# RamyunControlBoard.net
KiCad netlist of a schematic drawn in EAGLE
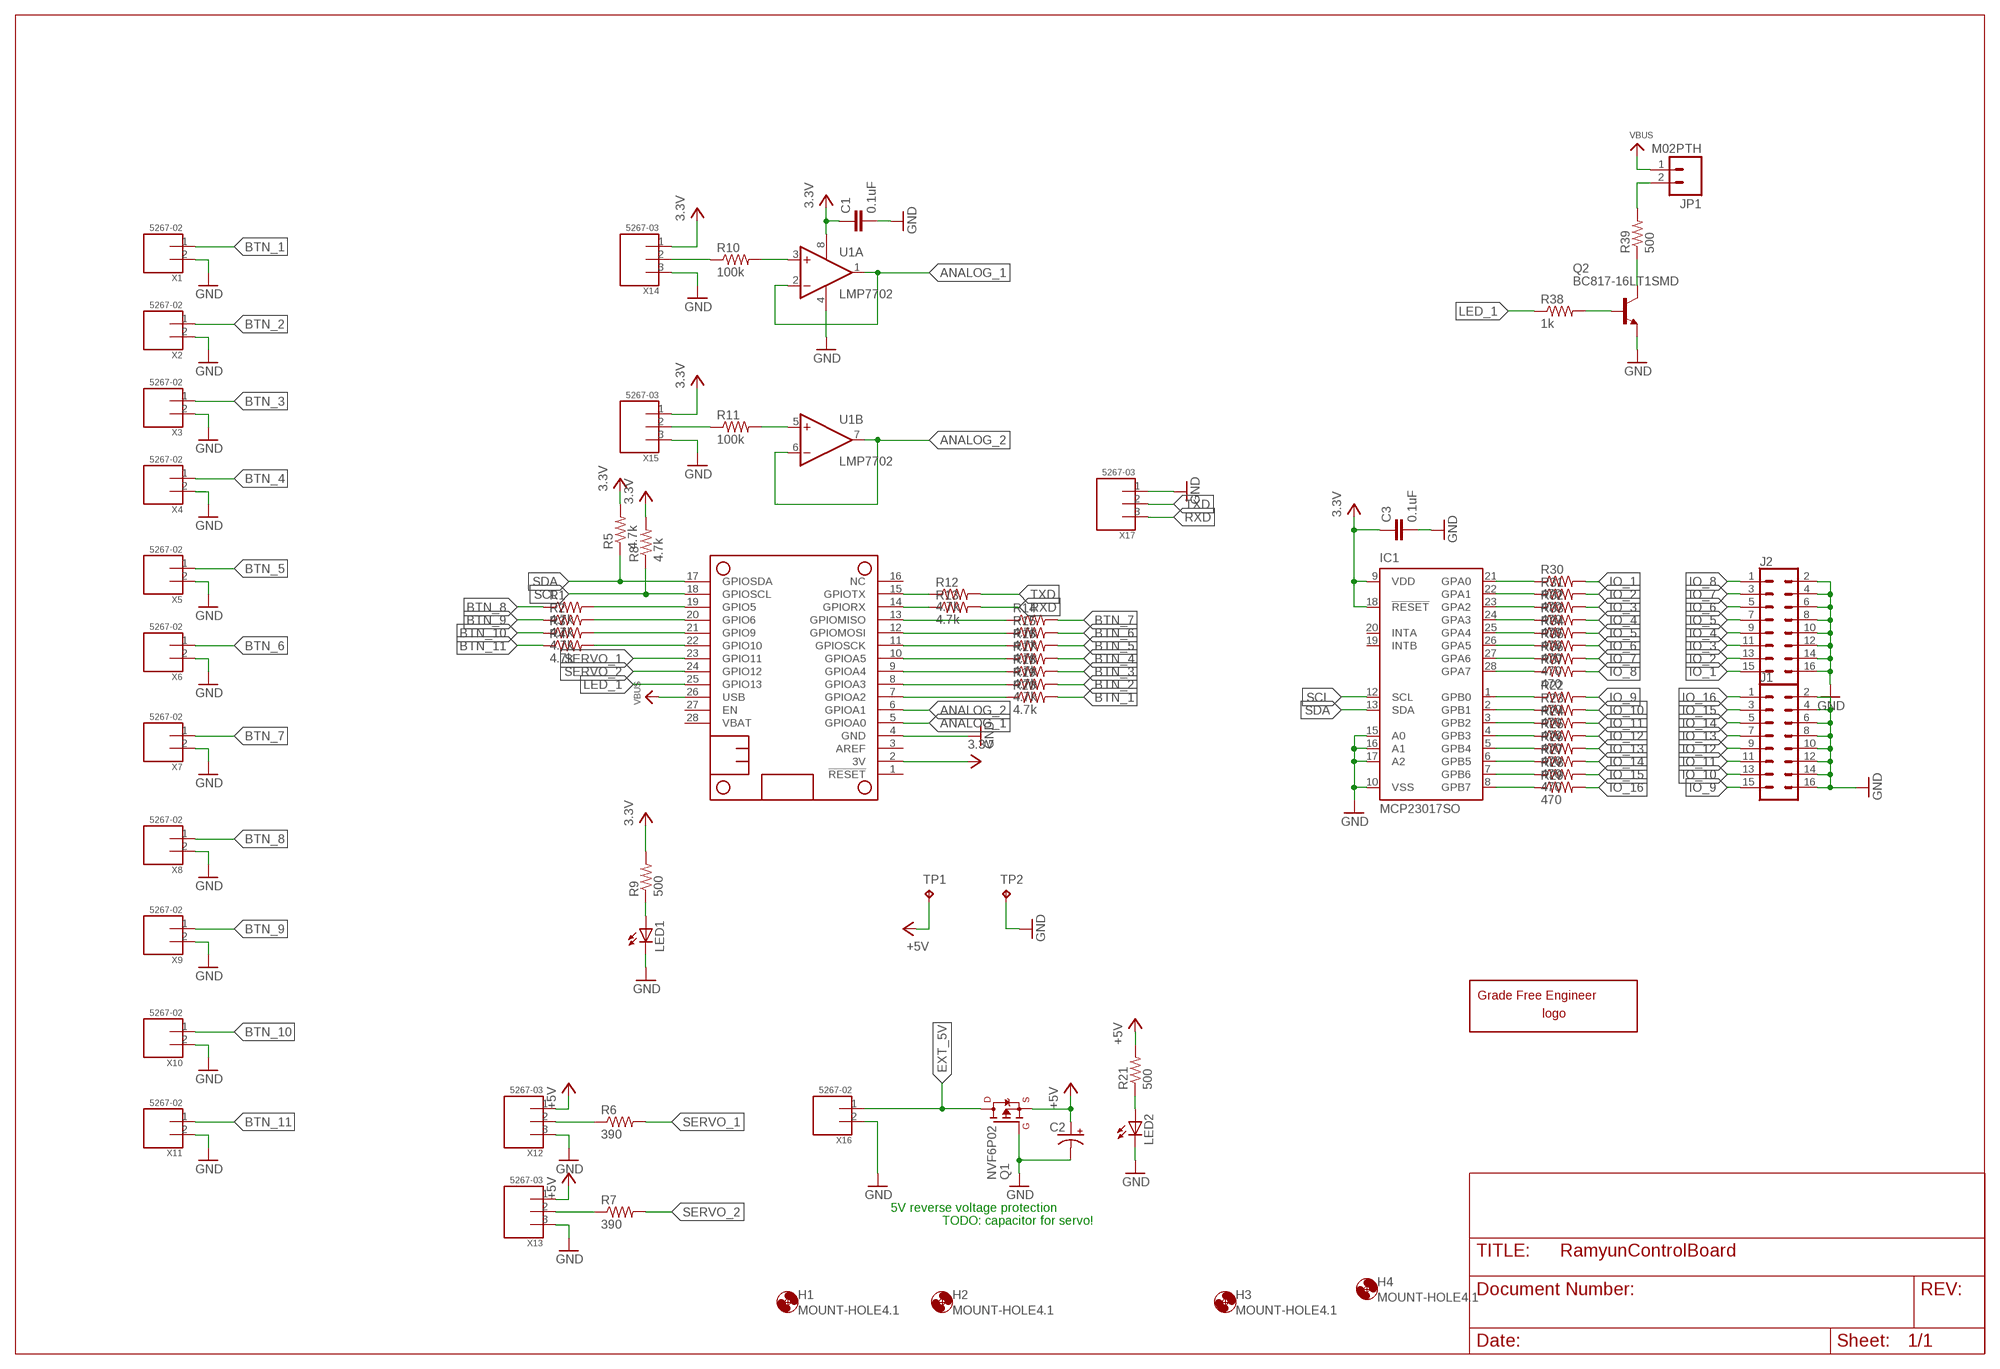
[diagram p0: schematic, sheet 1]

(export (version "E")
  (design (tool "Eeschema 10.0.6"))
  (components
    (comp (ref "C1")
      (value "0.1uF")
      (footprint "eagle-import:C0603(1608)_HANDSOLDER")
      (libsource (lib "eagle-import") (part "C0603(1608)_HAND"))
    )
    (comp (ref "C2")
      (value "CPOL-USE3.5-8")
      (footprint "eagle-import:E3,5-8")
      (libsource (lib "eagle-import") (part "CPOL-USE3.5-8"))
    )
    (comp (ref "C3")
      (value "0.1uF")
      (footprint "eagle-import:C0603(1608)_HANDSOLDER")
      (libsource (lib "eagle-import") (part "C0603(1608)_HAND"))
    )
    (comp (ref "H1")
      (value "MOUNT-HOLE4.1")
      (footprint "eagle-import:4,1")
      (libsource (lib "eagle-import") (part "MOUNT-HOLE4.1"))
    )
    (comp (ref "H2")
      (value "MOUNT-HOLE4.1")
      (footprint "eagle-import:4,1")
      (libsource (lib "eagle-import") (part "MOUNT-HOLE4.1"))
    )
    (comp (ref "H3")
      (value "MOUNT-HOLE4.1")
      (footprint "eagle-import:4,1")
      (libsource (lib "eagle-import") (part "MOUNT-HOLE4.1"))
    )
    (comp (ref "H4")
      (value "MOUNT-HOLE4.1")
      (footprint "eagle-import:4,1")
      (libsource (lib "eagle-import") (part "MOUNT-HOLE4.1"))
    )
    (comp (ref "IC1")
      (value "MCP23017SO")
      (footprint "eagle-import:SO28W")
      (libsource (lib "eagle-import") (part "MCP23017SO"))
    )
    (comp (ref "J1")
      (value "CONN_08X2")
      (footprint "eagle-import:2X8")
      (libsource (lib "eagle-import") (part "CONN_08X2"))
    )
    (comp (ref "J2")
      (value "CONN_08X2")
      (footprint "eagle-import:2X8")
      (libsource (lib "eagle-import") (part "CONN_08X2"))
    )
    (comp (ref "JP1")
      (value "M02PTH")
      (footprint "eagle-import:1X02")
      (libsource (lib "eagle-import") (part "M02PTH"))
    )
    (comp (ref "LED1")
      (value "LED3MM")
      (footprint "eagle-import:LED3MM")
      (libsource (lib "eagle-import") (part "LED3MM"))
    )
    (comp (ref "LED2")
      (value "LED3MM")
      (footprint "eagle-import:LED3MM")
      (libsource (lib "eagle-import") (part "LED3MM"))
    )
    (comp (ref "LOGO1")
      (value "GRADEFREELOGO-20")
      (footprint "eagle-import:GRADEFREELOGO-20")
      (libsource (lib "eagle-import") (part "GRADEFREELOGO-20"))
    )
    (comp (ref "MS1")
      (value "FEATHERWING_NODIM")
      (footprint "eagle-import:FEATHERWING_DIM")
      (libsource (lib "eagle-import") (part "FEATHERWING_NODIM"))
    )
    (comp (ref "Q1")
      (value "NVF6P02")
      (footprint "eagle-import:SOT223")
      (libsource (lib "eagle-import") (part "NVF6P02"))
    )
    (comp (ref "Q2")
      (value "BC817-16LT1SMD")
      (footprint "eagle-import:SOT23-BEC")
      (libsource (lib "eagle-import") (part "BC817SMD-16LT1"))
    )
    (comp (ref "R1")
      (value "4.7k")
      (footprint "eagle-import:R0603(1608)_HANDSOLDER")
      (libsource (lib "eagle-import") (part "R0603(1608)_HAND"))
    )
    (comp (ref "R2")
      (value "4.7k")
      (footprint "eagle-import:R0603(1608)_HANDSOLDER")
      (libsource (lib "eagle-import") (part "R0603(1608)_HAND"))
    )
    (comp (ref "R3")
      (value "4.7k")
      (footprint "eagle-import:R0603(1608)_HANDSOLDER")
      (libsource (lib "eagle-import") (part "R0603(1608)_HAND"))
    )
    (comp (ref "R4")
      (value "4.7k")
      (footprint "eagle-import:R0603(1608)_HANDSOLDER")
      (libsource (lib "eagle-import") (part "R0603(1608)_HAND"))
    )
    (comp (ref "R5")
      (value "4.7k")
      (footprint "eagle-import:R0603(1608)_HANDSOLDER")
      (libsource (lib "eagle-import") (part "R0603(1608)_HAND"))
    )
    (comp (ref "R6")
      (value "390")
      (footprint "eagle-import:R0603(1608)_HANDSOLDER")
      (libsource (lib "eagle-import") (part "R0603(1608)_HAND"))
    )
    (comp (ref "R7")
      (value "390")
      (footprint "eagle-import:R0603(1608)_HANDSOLDER")
      (libsource (lib "eagle-import") (part "R0603(1608)_HAND"))
    )
    (comp (ref "R8")
      (value "4.7k")
      (footprint "eagle-import:R0603(1608)_HANDSOLDER")
      (libsource (lib "eagle-import") (part "R0603(1608)_HAND"))
    )
    (comp (ref "R9")
      (value "500")
      (footprint "eagle-import:R0603(1608)_HANDSOLDER")
      (libsource (lib "eagle-import") (part "R0603(1608)_HAND"))
    )
    (comp (ref "R10")
      (value "100k")
      (footprint "eagle-import:R0603(1608)_HANDSOLDER")
      (libsource (lib "eagle-import") (part "R0603(1608)_HAND"))
    )
    (comp (ref "R11")
      (value "100k")
      (footprint "eagle-import:R0603(1608)_HANDSOLDER")
      (libsource (lib "eagle-import") (part "R0603(1608)_HAND"))
    )
    (comp (ref "R12")
      (value "4.7k")
      (footprint "eagle-import:R0603(1608)_HANDSOLDER")
      (libsource (lib "eagle-import") (part "R0603(1608)_HAND"))
    )
    (comp (ref "R13")
      (value "4.7k")
      (footprint "eagle-import:R0603(1608)_HANDSOLDER")
      (libsource (lib "eagle-import") (part "R0603(1608)_HAND"))
    )
    (comp (ref "R14")
      (value "4.7k")
      (footprint "eagle-import:R0603(1608)_HANDSOLDER")
      (libsource (lib "eagle-import") (part "R0603(1608)_HAND"))
    )
    (comp (ref "R15")
      (value "4.7k")
      (footprint "eagle-import:R0603(1608)_HANDSOLDER")
      (libsource (lib "eagle-import") (part "R0603(1608)_HAND"))
    )
    (comp (ref "R16")
      (value "4.7k")
      (footprint "eagle-import:R0603(1608)_HANDSOLDER")
      (libsource (lib "eagle-import") (part "R0603(1608)_HAND"))
    )
    (comp (ref "R17")
      (value "4.7k")
      (footprint "eagle-import:R0603(1608)_HANDSOLDER")
      (libsource (lib "eagle-import") (part "R0603(1608)_HAND"))
    )
    (comp (ref "R18")
      (value "4.7k")
      (footprint "eagle-import:R0603(1608)_HANDSOLDER")
      (libsource (lib "eagle-import") (part "R0603(1608)_HAND"))
    )
    (comp (ref "R19")
      (value "4.7k")
      (footprint "eagle-import:R0603(1608)_HANDSOLDER")
      (libsource (lib "eagle-import") (part "R0603(1608)_HAND"))
    )
    (comp (ref "R20")
      (value "4.7k")
      (footprint "eagle-import:R0603(1608)_HANDSOLDER")
      (libsource (lib "eagle-import") (part "R0603(1608)_HAND"))
    )
    (comp (ref "R21")
      (value "500")
      (footprint "eagle-import:R0603(1608)_HANDSOLDER")
      (libsource (lib "eagle-import") (part "R0603(1608)_HAND"))
    )
    (comp (ref "R22")
      (value "470")
      (footprint "eagle-import:R0603(1608)_HANDSOLDER")
      (libsource (lib "eagle-import") (part "R0603(1608)_HAND"))
    )
    (comp (ref "R23")
      (value "470")
      (footprint "eagle-import:R0603(1608)_HANDSOLDER")
      (libsource (lib "eagle-import") (part "R0603(1608)_HAND"))
    )
    (comp (ref "R24")
      (value "470")
      (footprint "eagle-import:R0603(1608)_HANDSOLDER")
      (libsource (lib "eagle-import") (part "R0603(1608)_HAND"))
    )
    (comp (ref "R25")
      (value "470")
      (footprint "eagle-import:R0603(1608)_HANDSOLDER")
      (libsource (lib "eagle-import") (part "R0603(1608)_HAND"))
    )
    (comp (ref "R26")
      (value "470")
      (footprint "eagle-import:R0603(1608)_HANDSOLDER")
      (libsource (lib "eagle-import") (part "R0603(1608)_HAND"))
    )
    (comp (ref "R27")
      (value "470")
      (footprint "eagle-import:R0603(1608)_HANDSOLDER")
      (libsource (lib "eagle-import") (part "R0603(1608)_HAND"))
    )
    (comp (ref "R28")
      (value "470")
      (footprint "eagle-import:R0603(1608)_HANDSOLDER")
      (libsource (lib "eagle-import") (part "R0603(1608)_HAND"))
    )
    (comp (ref "R29")
      (value "470")
      (footprint "eagle-import:R0603(1608)_HANDSOLDER")
      (libsource (lib "eagle-import") (part "R0603(1608)_HAND"))
    )
    (comp (ref "R30")
      (value "470")
      (footprint "eagle-import:R0603(1608)_HANDSOLDER")
      (libsource (lib "eagle-import") (part "R0603(1608)_HAND"))
    )
    (comp (ref "R31")
      (value "470")
      (footprint "eagle-import:R0603(1608)_HANDSOLDER")
      (libsource (lib "eagle-import") (part "R0603(1608)_HAND"))
    )
    (comp (ref "R32")
      (value "470")
      (footprint "eagle-import:R0603(1608)_HANDSOLDER")
      (libsource (lib "eagle-import") (part "R0603(1608)_HAND"))
    )
    (comp (ref "R33")
      (value "470")
      (footprint "eagle-import:R0603(1608)_HANDSOLDER")
      (libsource (lib "eagle-import") (part "R0603(1608)_HAND"))
    )
    (comp (ref "R34")
      (value "470")
      (footprint "eagle-import:R0603(1608)_HANDSOLDER")
      (libsource (lib "eagle-import") (part "R0603(1608)_HAND"))
    )
    (comp (ref "R35")
      (value "470")
      (footprint "eagle-import:R0603(1608)_HANDSOLDER")
      (libsource (lib "eagle-import") (part "R0603(1608)_HAND"))
    )
    (comp (ref "R36")
      (value "470")
      (footprint "eagle-import:R0603(1608)_HANDSOLDER")
      (libsource (lib "eagle-import") (part "R0603(1608)_HAND"))
    )
    (comp (ref "R37")
      (value "470")
      (footprint "eagle-import:R0603(1608)_HANDSOLDER")
      (libsource (lib "eagle-import") (part "R0603(1608)_HAND"))
    )
    (comp (ref "R38")
      (value "1k")
      (footprint "eagle-import:R0603(1608)_HANDSOLDER")
      (libsource (lib "eagle-import") (part "R0603(1608)_HAND"))
    )
    (comp (ref "R39")
      (value "500")
      (footprint "eagle-import:R0603(1608)_HANDSOLDER")
      (libsource (lib "eagle-import") (part "R0603(1608)_HAND"))
    )
    (comp (ref "TP1")
      (value "TP-5010")
      (footprint "eagle-import:TP-5010")
      (libsource (lib "eagle-import") (part "TP-5010"))
    )
    (comp (ref "TP2")
      (value "TP-5010")
      (footprint "eagle-import:TP-5010")
      (libsource (lib "eagle-import") (part "TP-5010"))
    )
    (comp (ref "U1")
      (value "LMP7702")
      (footprint "eagle-import:DGK_S-DPSO-G8")
      (libsource (lib "eagle-import") (part "LMP7702"))
    )
    (comp (ref "X1")
      (value "5267-02")
      (footprint "eagle-import:5267-02")
      (libsource (lib "eagle-import") (part "5267-02"))
    )
    (comp (ref "X2")
      (value "5267-02")
      (footprint "eagle-import:5267-02")
      (libsource (lib "eagle-import") (part "5267-02"))
    )
    (comp (ref "X3")
      (value "5267-02")
      (footprint "eagle-import:5267-02")
      (libsource (lib "eagle-import") (part "5267-02"))
    )
    (comp (ref "X4")
      (value "5267-02")
      (footprint "eagle-import:5267-02")
      (libsource (lib "eagle-import") (part "5267-02"))
    )
    (comp (ref "X5")
      (value "5267-02")
      (footprint "eagle-import:5267-02")
      (libsource (lib "eagle-import") (part "5267-02"))
    )
    (comp (ref "X6")
      (value "5267-02")
      (footprint "eagle-import:5267-02")
      (libsource (lib "eagle-import") (part "5267-02"))
    )
    (comp (ref "X7")
      (value "5267-02")
      (footprint "eagle-import:5267-02")
      (libsource (lib "eagle-import") (part "5267-02"))
    )
    (comp (ref "X8")
      (value "5267-02")
      (footprint "eagle-import:5267-02")
      (libsource (lib "eagle-import") (part "5267-02"))
    )
    (comp (ref "X9")
      (value "5267-02")
      (footprint "eagle-import:5267-02")
      (libsource (lib "eagle-import") (part "5267-02"))
    )
    (comp (ref "X10")
      (value "5267-02")
      (footprint "eagle-import:5267-02")
      (libsource (lib "eagle-import") (part "5267-02"))
    )
    (comp (ref "X11")
      (value "5267-02")
      (footprint "eagle-import:5267-02")
      (libsource (lib "eagle-import") (part "5267-02"))
    )
    (comp (ref "X12")
      (value "5267-03")
      (footprint "eagle-import:5267-03")
      (libsource (lib "eagle-import") (part "5267-03"))
    )
    (comp (ref "X13")
      (value "5267-03")
      (footprint "eagle-import:5267-03")
      (libsource (lib "eagle-import") (part "5267-03"))
    )
    (comp (ref "X14")
      (value "5267-03")
      (footprint "eagle-import:5267-03")
      (libsource (lib "eagle-import") (part "5267-03"))
    )
    (comp (ref "X15")
      (value "5267-03")
      (footprint "eagle-import:5267-03")
      (libsource (lib "eagle-import") (part "5267-03"))
    )
    (comp (ref "X16")
      (value "5267-02")
      (footprint "eagle-import:5267-02")
      (libsource (lib "eagle-import") (part "5267-02"))
    )
    (comp (ref "X17")
      (value "5267-03")
      (footprint "eagle-import:5267-03")
      (libsource (lib "eagle-import") (part "5267-03"))
    )
  )
  (nets
    (net (code "1") (name "+5V") (class "Default")
      (node (ref "C2") (pin "+") (pinfunction "+_+") (pintype "passive"))
      (node (ref "Q1") (pin "3") (pinfunction "S_3") (pintype "passive"))
      (node (ref "R21") (pin "2") (pinfunction "2_2") (pintype "passive"))
      (node (ref "TP1") (pin "TP") (pinfunction "TP_TP") (pintype "input"))
      (node (ref "X12") (pin "1") (pinfunction "1_1") (pintype "bidirectional"))
      (node (ref "X13") (pin "1") (pinfunction "1_1") (pintype "bidirectional"))
    )
    (net (code "2") (name "/VBAT") (class "Default")
      (node (ref "MS1") (pin "28") (pinfunction "VBAT_28") (pintype "power_in"))
    )
    (net (code "3") (name "3.3V") (class "Default")
      (node (ref "C1") (pin "1") (pinfunction "1_1") (pintype "passive"))
      (node (ref "C3") (pin "1") (pinfunction "1_1") (pintype "passive"))
      (node (ref "IC1") (pin "18") (pinfunction "~{RESET}_18") (pintype "input"))
      (node (ref "IC1") (pin "9") (pinfunction "VDD_9") (pintype "power_in"))
      (node (ref "MS1") (pin "2") (pinfunction "3V_2") (pintype "power_in"))
      (node (ref "R5") (pin "2") (pinfunction "2_2") (pintype "passive"))
      (node (ref "R8") (pin "2") (pinfunction "2_2") (pintype "passive"))
      (node (ref "R9") (pin "2") (pinfunction "2_2") (pintype "passive"))
      (node (ref "U1") (pin "8") (pinfunction "V+_8") (pintype "power_in"))
      (node (ref "X14") (pin "1") (pinfunction "1_1") (pintype "bidirectional"))
      (node (ref "X15") (pin "1") (pinfunction "1_1") (pintype "bidirectional"))
    )
    (net (code "4") (name "ANALOG_1") (class "Default")
      (node (ref "MS1") (pin "5") (pinfunction "GPIOA0_5") (pintype "bidirectional"))
      (node (ref "U1") (pin "1") (pinfunction "OUT_1") (pintype "output"))
      (node (ref "U1") (pin "2") (pinfunction "-IN_2") (pintype "input"))
    )
    (net (code "5") (name "ANALOG_2") (class "Default")
      (node (ref "MS1") (pin "6") (pinfunction "GPIOA1_6") (pintype "bidirectional"))
      (node (ref "U1") (pin "6") (pinfunction "-IN_6") (pintype "input"))
      (node (ref "U1") (pin "7") (pinfunction "OUT_7") (pintype "output"))
    )
    (net (code "6") (name "BTN_1") (class "Default")
      (node (ref "R20") (pin "2") (pinfunction "2_2") (pintype "passive"))
      (node (ref "X1") (pin "1") (pinfunction "1_1") (pintype "bidirectional"))
    )
    (net (code "7") (name "BTN_2") (class "Default")
      (node (ref "R19") (pin "2") (pinfunction "2_2") (pintype "passive"))
      (node (ref "X2") (pin "1") (pinfunction "1_1") (pintype "bidirectional"))
    )
    (net (code "8") (name "BTN_3") (class "Default")
      (node (ref "R18") (pin "2") (pinfunction "2_2") (pintype "passive"))
      (node (ref "X3") (pin "1") (pinfunction "1_1") (pintype "bidirectional"))
    )
    (net (code "9") (name "BTN_4") (class "Default")
      (node (ref "R17") (pin "2") (pinfunction "2_2") (pintype "passive"))
      (node (ref "X4") (pin "1") (pinfunction "1_1") (pintype "bidirectional"))
    )
    (net (code "10") (name "BTN_5") (class "Default")
      (node (ref "R16") (pin "2") (pinfunction "2_2") (pintype "passive"))
      (node (ref "X5") (pin "1") (pinfunction "1_1") (pintype "bidirectional"))
    )
    (net (code "11") (name "BTN_6") (class "Default")
      (node (ref "R15") (pin "2") (pinfunction "2_2") (pintype "passive"))
      (node (ref "X6") (pin "1") (pinfunction "1_1") (pintype "bidirectional"))
    )
    (net (code "12") (name "BTN_7") (class "Default")
      (node (ref "R14") (pin "2") (pinfunction "2_2") (pintype "passive"))
      (node (ref "X7") (pin "1") (pinfunction "1_1") (pintype "bidirectional"))
    )
    (net (code "13") (name "BTN_8") (class "Default")
      (node (ref "R1") (pin "1") (pinfunction "1_1") (pintype "passive"))
      (node (ref "X8") (pin "1") (pinfunction "1_1") (pintype "bidirectional"))
    )
    (net (code "14") (name "BTN_9") (class "Default")
      (node (ref "R2") (pin "1") (pinfunction "1_1") (pintype "passive"))
      (node (ref "X9") (pin "1") (pinfunction "1_1") (pintype "bidirectional"))
    )
    (net (code "15") (name "BTN_10") (class "Default")
      (node (ref "R3") (pin "1") (pinfunction "1_1") (pintype "passive"))
      (node (ref "X10") (pin "1") (pinfunction "1_1") (pintype "bidirectional"))
    )
    (net (code "16") (name "BTN_11") (class "Default")
      (node (ref "R4") (pin "1") (pinfunction "1_1") (pintype "passive"))
      (node (ref "X11") (pin "1") (pinfunction "1_1") (pintype "bidirectional"))
    )
    (net (code "17") (name "EXT_5V") (class "Default")
      (node (ref "Q1") (pin "2") (pinfunction "D_2") (pintype "passive"))
      (node (ref "Q1") (pin "4") (pinfunction "D_4") (pintype "passive"))
      (node (ref "X16") (pin "1") (pinfunction "1_1") (pintype "bidirectional"))
    )
    (net (code "18") (name "GND") (class "Default")
      (node (ref "C1") (pin "2") (pinfunction "2_2") (pintype "passive"))
      (node (ref "C2") (pin "-") (pinfunction "-_-") (pintype "passive"))
      (node (ref "C3") (pin "2") (pinfunction "2_2") (pintype "passive"))
      (node (ref "IC1") (pin "10") (pinfunction "VSS_10") (pintype "power_in"))
      (node (ref "IC1") (pin "15") (pinfunction "A0_15") (pintype "input"))
      (node (ref "IC1") (pin "16") (pinfunction "A1_16") (pintype "input"))
      (node (ref "IC1") (pin "17") (pinfunction "A2_17") (pintype "input"))
      (node (ref "J1") (pin "10") (pinfunction "10_10") (pintype "passive"))
      (node (ref "J1") (pin "12") (pinfunction "12_12") (pintype "passive"))
      (node (ref "J1") (pin "14") (pinfunction "14_14") (pintype "passive"))
      (node (ref "J1") (pin "16") (pinfunction "16_16") (pintype "passive"))
      (node (ref "J1") (pin "2") (pinfunction "2_2") (pintype "passive"))
      (node (ref "J1") (pin "4") (pinfunction "4_4") (pintype "passive"))
      (node (ref "J1") (pin "6") (pinfunction "6_6") (pintype "passive"))
      (node (ref "J1") (pin "8") (pinfunction "8_8") (pintype "passive"))
      (node (ref "J2") (pin "10") (pinfunction "10_10") (pintype "passive"))
      (node (ref "J2") (pin "12") (pinfunction "12_12") (pintype "passive"))
      (node (ref "J2") (pin "14") (pinfunction "14_14") (pintype "passive"))
      (node (ref "J2") (pin "16") (pinfunction "16_16") (pintype "passive"))
      (node (ref "J2") (pin "2") (pinfunction "2_2") (pintype "passive"))
      (node (ref "J2") (pin "4") (pinfunction "4_4") (pintype "passive"))
      (node (ref "J2") (pin "6") (pinfunction "6_6") (pintype "passive"))
      (node (ref "J2") (pin "8") (pinfunction "8_8") (pintype "passive"))
      (node (ref "LED1") (pin "K") (pinfunction "C_K") (pintype "passive"))
      (node (ref "LED2") (pin "K") (pinfunction "C_K") (pintype "passive"))
      (node (ref "MS1") (pin "4") (pinfunction "GND_4") (pintype "power_in"))
      (node (ref "Q1") (pin "1") (pinfunction "G_1") (pintype "passive"))
      (node (ref "Q2") (pin "E") (pinfunction "E_E") (pintype "passive"))
      (node (ref "TP2") (pin "TP") (pinfunction "TP_TP") (pintype "input"))
      (node (ref "U1") (pin "4") (pinfunction "V-_4") (pintype "power_in"))
      (node (ref "X1") (pin "2") (pinfunction "2_2") (pintype "bidirectional"))
      (node (ref "X10") (pin "2") (pinfunction "2_2") (pintype "bidirectional"))
      (node (ref "X11") (pin "2") (pinfunction "2_2") (pintype "bidirectional"))
      (node (ref "X12") (pin "3") (pinfunction "3_3") (pintype "bidirectional"))
      (node (ref "X13") (pin "3") (pinfunction "3_3") (pintype "bidirectional"))
      (node (ref "X14") (pin "3") (pinfunction "3_3") (pintype "bidirectional"))
      (node (ref "X15") (pin "3") (pinfunction "3_3") (pintype "bidirectional"))
      (node (ref "X16") (pin "2") (pinfunction "2_2") (pintype "bidirectional"))
      (node (ref "X17") (pin "1") (pinfunction "1_1") (pintype "bidirectional"))
      (node (ref "X2") (pin "2") (pinfunction "2_2") (pintype "bidirectional"))
      (node (ref "X3") (pin "2") (pinfunction "2_2") (pintype "bidirectional"))
      (node (ref "X4") (pin "2") (pinfunction "2_2") (pintype "bidirectional"))
      (node (ref "X5") (pin "2") (pinfunction "2_2") (pintype "bidirectional"))
      (node (ref "X6") (pin "2") (pinfunction "2_2") (pintype "bidirectional"))
      (node (ref "X7") (pin "2") (pinfunction "2_2") (pintype "bidirectional"))
      (node (ref "X8") (pin "2") (pinfunction "2_2") (pintype "bidirectional"))
      (node (ref "X9") (pin "2") (pinfunction "2_2") (pintype "bidirectional"))
    )
    (net (code "19") (name "IO_1") (class "Default")
      (node (ref "J2") (pin "15") (pinfunction "15_15") (pintype "passive"))
      (node (ref "R30") (pin "2") (pinfunction "2_2") (pintype "passive"))
    )
    (net (code "20") (name "IO_2") (class "Default")
      (node (ref "J2") (pin "13") (pinfunction "13_13") (pintype "passive"))
      (node (ref "R31") (pin "2") (pinfunction "2_2") (pintype "passive"))
    )
    (net (code "21") (name "IO_3") (class "Default")
      (node (ref "J2") (pin "11") (pinfunction "11_11") (pintype "passive"))
      (node (ref "R32") (pin "2") (pinfunction "2_2") (pintype "passive"))
    )
    (net (code "22") (name "IO_4") (class "Default")
      (node (ref "J2") (pin "9") (pinfunction "9_9") (pintype "passive"))
      (node (ref "R33") (pin "2") (pinfunction "2_2") (pintype "passive"))
    )
    (net (code "23") (name "IO_5") (class "Default")
      (node (ref "J2") (pin "7") (pinfunction "7_7") (pintype "passive"))
      (node (ref "R34") (pin "2") (pinfunction "2_2") (pintype "passive"))
    )
    (net (code "24") (name "IO_6") (class "Default")
      (node (ref "J2") (pin "5") (pinfunction "5_5") (pintype "passive"))
      (node (ref "R35") (pin "2") (pinfunction "2_2") (pintype "passive"))
    )
    (net (code "25") (name "IO_7") (class "Default")
      (node (ref "J2") (pin "3") (pinfunction "3_3") (pintype "passive"))
      (node (ref "R36") (pin "2") (pinfunction "2_2") (pintype "passive"))
    )
    (net (code "26") (name "IO_8") (class "Default")
      (node (ref "J2") (pin "1") (pinfunction "1_1") (pintype "passive"))
      (node (ref "R37") (pin "2") (pinfunction "2_2") (pintype "passive"))
    )
    (net (code "27") (name "IO_9") (class "Default")
      (node (ref "J1") (pin "15") (pinfunction "15_15") (pintype "passive"))
      (node (ref "R22") (pin "2") (pinfunction "2_2") (pintype "passive"))
    )
    (net (code "28") (name "IO_10") (class "Default")
      (node (ref "J1") (pin "13") (pinfunction "13_13") (pintype "passive"))
      (node (ref "R23") (pin "2") (pinfunction "2_2") (pintype "passive"))
    )
    (net (code "29") (name "IO_11") (class "Default")
      (node (ref "J1") (pin "11") (pinfunction "11_11") (pintype "passive"))
      (node (ref "R24") (pin "2") (pinfunction "2_2") (pintype "passive"))
    )
    (net (code "30") (name "IO_12") (class "Default")
      (node (ref "J1") (pin "9") (pinfunction "9_9") (pintype "passive"))
      (node (ref "R25") (pin "2") (pinfunction "2_2") (pintype "passive"))
    )
    (net (code "31") (name "IO_13") (class "Default")
      (node (ref "J1") (pin "7") (pinfunction "7_7") (pintype "passive"))
      (node (ref "R26") (pin "2") (pinfunction "2_2") (pintype "passive"))
    )
    (net (code "32") (name "IO_14") (class "Default")
      (node (ref "J1") (pin "5") (pinfunction "5_5") (pintype "passive"))
      (node (ref "R27") (pin "2") (pinfunction "2_2") (pintype "passive"))
    )
    (net (code "33") (name "IO_15") (class "Default")
      (node (ref "J1") (pin "3") (pinfunction "3_3") (pintype "passive"))
      (node (ref "R28") (pin "2") (pinfunction "2_2") (pintype "passive"))
    )
    (net (code "34") (name "IO_16") (class "Default")
      (node (ref "J1") (pin "1") (pinfunction "1_1") (pintype "passive"))
      (node (ref "R29") (pin "2") (pinfunction "2_2") (pintype "passive"))
    )
    (net (code "35") (name "LED_1") (class "Default")
      (node (ref "MS1") (pin "25") (pinfunction "GPIO13_25") (pintype "bidirectional"))
      (node (ref "R38") (pin "1") (pinfunction "1_1") (pintype "passive"))
    )
    (net (code "36") (name "Net-(IC1-GPA0)") (class "Default")
      (node (ref "IC1") (pin "21") (pinfunction "GPA0_21") (pintype "bidirectional"))
      (node (ref "R30") (pin "1") (pinfunction "1_1") (pintype "passive"))
    )
    (net (code "37") (name "Net-(IC1-GPA1)") (class "Default")
      (node (ref "IC1") (pin "22") (pinfunction "GPA1_22") (pintype "bidirectional"))
      (node (ref "R31") (pin "1") (pinfunction "1_1") (pintype "passive"))
    )
    (net (code "38") (name "Net-(IC1-GPA2)") (class "Default")
      (node (ref "IC1") (pin "23") (pinfunction "GPA2_23") (pintype "bidirectional"))
      (node (ref "R32") (pin "1") (pinfunction "1_1") (pintype "passive"))
    )
    (net (code "39") (name "Net-(IC1-GPA3)") (class "Default")
      (node (ref "IC1") (pin "24") (pinfunction "GPA3_24") (pintype "bidirectional"))
      (node (ref "R33") (pin "1") (pinfunction "1_1") (pintype "passive"))
    )
    (net (code "40") (name "Net-(IC1-GPA4)") (class "Default")
      (node (ref "IC1") (pin "25") (pinfunction "GPA4_25") (pintype "bidirectional"))
      (node (ref "R34") (pin "1") (pinfunction "1_1") (pintype "passive"))
    )
    (net (code "41") (name "Net-(IC1-GPA5)") (class "Default")
      (node (ref "IC1") (pin "26") (pinfunction "GPA5_26") (pintype "bidirectional"))
      (node (ref "R35") (pin "1") (pinfunction "1_1") (pintype "passive"))
    )
    (net (code "42") (name "Net-(IC1-GPA6)") (class "Default")
      (node (ref "IC1") (pin "27") (pinfunction "GPA6_27") (pintype "bidirectional"))
      (node (ref "R36") (pin "1") (pinfunction "1_1") (pintype "passive"))
    )
    (net (code "43") (name "Net-(IC1-GPA7)") (class "Default")
      (node (ref "IC1") (pin "28") (pinfunction "GPA7_28") (pintype "bidirectional"))
      (node (ref "R37") (pin "1") (pinfunction "1_1") (pintype "passive"))
    )
    (net (code "44") (name "Net-(IC1-GPB0)") (class "Default")
      (node (ref "IC1") (pin "1") (pinfunction "GPB0_1") (pintype "bidirectional"))
      (node (ref "R22") (pin "1") (pinfunction "1_1") (pintype "passive"))
    )
    (net (code "45") (name "Net-(IC1-GPB1)") (class "Default")
      (node (ref "IC1") (pin "2") (pinfunction "GPB1_2") (pintype "bidirectional"))
      (node (ref "R23") (pin "1") (pinfunction "1_1") (pintype "passive"))
    )
    (net (code "46") (name "Net-(IC1-GPB2)") (class "Default")
      (node (ref "IC1") (pin "3") (pinfunction "GPB2_3") (pintype "bidirectional"))
      (node (ref "R24") (pin "1") (pinfunction "1_1") (pintype "passive"))
    )
    (net (code "47") (name "Net-(IC1-GPB3)") (class "Default")
      (node (ref "IC1") (pin "4") (pinfunction "GPB3_4") (pintype "bidirectional"))
      (node (ref "R25") (pin "1") (pinfunction "1_1") (pintype "passive"))
    )
    (net (code "48") (name "Net-(IC1-GPB4)") (class "Default")
      (node (ref "IC1") (pin "5") (pinfunction "GPB4_5") (pintype "bidirectional"))
      (node (ref "R26") (pin "1") (pinfunction "1_1") (pintype "passive"))
    )
    (net (code "49") (name "Net-(IC1-GPB5)") (class "Default")
      (node (ref "IC1") (pin "6") (pinfunction "GPB5_6") (pintype "bidirectional"))
      (node (ref "R27") (pin "1") (pinfunction "1_1") (pintype "passive"))
    )
    (net (code "50") (name "Net-(IC1-GPB6)") (class "Default")
      (node (ref "IC1") (pin "7") (pinfunction "GPB6_7") (pintype "bidirectional"))
      (node (ref "R28") (pin "1") (pinfunction "1_1") (pintype "passive"))
    )
    (net (code "51") (name "Net-(IC1-GPB7)") (class "Default")
      (node (ref "IC1") (pin "8") (pinfunction "GPB7_8") (pintype "bidirectional"))
      (node (ref "R29") (pin "1") (pinfunction "1_1") (pintype "passive"))
    )
    (net (code "52") (name "Net-(JP1-Pad2)") (class "Default")
      (node (ref "JP1") (pin "2") (pinfunction "2_2") (pintype "passive"))
      (node (ref "R39") (pin "2") (pinfunction "2_2") (pintype "passive"))
    )
    (net (code "53") (name "Net-(LED1-PadA)") (class "Default")
      (node (ref "LED1") (pin "A") (pinfunction "A_A") (pintype "passive"))
      (node (ref "R9") (pin "1") (pinfunction "1_1") (pintype "passive"))
    )
    (net (code "54") (name "Net-(LED2-PadA)") (class "Default")
      (node (ref "LED2") (pin "A") (pinfunction "A_A") (pintype "passive"))
      (node (ref "R21") (pin "1") (pinfunction "1_1") (pintype "passive"))
    )
    (net (code "55") (name "Net-(MS1-GPIO5)") (class "Default")
      (node (ref "MS1") (pin "19") (pinfunction "GPIO5_19") (pintype "bidirectional"))
      (node (ref "R1") (pin "2") (pinfunction "2_2") (pintype "passive"))
    )
    (net (code "56") (name "Net-(MS1-GPIO6)") (class "Default")
      (node (ref "MS1") (pin "20") (pinfunction "GPIO6_20") (pintype "bidirectional"))
      (node (ref "R2") (pin "2") (pinfunction "2_2") (pintype "passive"))
    )
    (net (code "57") (name "Net-(MS1-GPIO9)") (class "Default")
      (node (ref "MS1") (pin "21") (pinfunction "GPIO9_21") (pintype "bidirectional"))
      (node (ref "R3") (pin "2") (pinfunction "2_2") (pintype "passive"))
    )
    (net (code "58") (name "Net-(MS1-GPIO10)") (class "Default")
      (node (ref "MS1") (pin "22") (pinfunction "GPIO10_22") (pintype "bidirectional"))
      (node (ref "R4") (pin "2") (pinfunction "2_2") (pintype "passive"))
    )
    (net (code "59") (name "Net-(MS1-GPIOA2)") (class "Default")
      (node (ref "MS1") (pin "7") (pinfunction "GPIOA2_7") (pintype "bidirectional"))
      (node (ref "R20") (pin "1") (pinfunction "1_1") (pintype "passive"))
    )
    (net (code "60") (name "Net-(MS1-GPIOA3)") (class "Default")
      (node (ref "MS1") (pin "8") (pinfunction "GPIOA3_8") (pintype "bidirectional"))
      (node (ref "R19") (pin "1") (pinfunction "1_1") (pintype "passive"))
    )
    (net (code "61") (name "Net-(MS1-GPIOA4)") (class "Default")
      (node (ref "MS1") (pin "9") (pinfunction "GPIOA4_9") (pintype "bidirectional"))
      (node (ref "R18") (pin "1") (pinfunction "1_1") (pintype "passive"))
    )
    (net (code "62") (name "Net-(MS1-GPIOA5)") (class "Default")
      (node (ref "MS1") (pin "10") (pinfunction "GPIOA5_10") (pintype "bidirectional"))
      (node (ref "R17") (pin "1") (pinfunction "1_1") (pintype "passive"))
    )
    (net (code "63") (name "Net-(MS1-GPIOMISO)") (class "Default")
      (node (ref "MS1") (pin "13") (pinfunction "GPIOMISO_13") (pintype "bidirectional"))
      (node (ref "R14") (pin "1") (pinfunction "1_1") (pintype "passive"))
    )
    (net (code "64") (name "Net-(MS1-GPIOMOSI)") (class "Default")
      (node (ref "MS1") (pin "12") (pinfunction "GPIOMOSI_12") (pintype "bidirectional"))
      (node (ref "R15") (pin "1") (pinfunction "1_1") (pintype "passive"))
    )
    (net (code "65") (name "Net-(MS1-GPIORX)") (class "Default")
      (node (ref "MS1") (pin "14") (pinfunction "GPIORX_14") (pintype "bidirectional"))
      (node (ref "R13") (pin "1") (pinfunction "1_1") (pintype "passive"))
    )
    (net (code "66") (name "Net-(MS1-GPIOSCK)") (class "Default")
      (node (ref "MS1") (pin "11") (pinfunction "GPIOSCK_11") (pintype "bidirectional"))
      (node (ref "R16") (pin "1") (pinfunction "1_1") (pintype "passive"))
    )
    (net (code "67") (name "Net-(MS1-GPIOTX)") (class "Default")
      (node (ref "MS1") (pin "15") (pinfunction "GPIOTX_15") (pintype "bidirectional"))
      (node (ref "R12") (pin "1") (pinfunction "1_1") (pintype "passive"))
    )
    (net (code "68") (name "Net-(Q2-PadB)") (class "Default")
      (node (ref "Q2") (pin "B") (pinfunction "B_B") (pintype "passive"))
      (node (ref "R38") (pin "2") (pinfunction "2_2") (pintype "passive"))
    )
    (net (code "69") (name "Net-(Q2-PadC)") (class "Default")
      (node (ref "Q2") (pin "C") (pinfunction "C_C") (pintype "passive"))
      (node (ref "R39") (pin "1") (pinfunction "1_1") (pintype "passive"))
    )
    (net (code "70") (name "Net-(R6-Pad1)") (class "Default")
      (node (ref "R6") (pin "1") (pinfunction "1_1") (pintype "passive"))
      (node (ref "X12") (pin "2") (pinfunction "2_2") (pintype "bidirectional"))
    )
    (net (code "71") (name "Net-(R7-Pad1)") (class "Default")
      (node (ref "R7") (pin "1") (pinfunction "1_1") (pintype "passive"))
      (node (ref "X13") (pin "2") (pinfunction "2_2") (pintype "bidirectional"))
    )
    (net (code "72") (name "Net-(R10-Pad1)") (class "Default")
      (node (ref "R10") (pin "1") (pinfunction "1_1") (pintype "passive"))
      (node (ref "X14") (pin "2") (pinfunction "2_2") (pintype "bidirectional"))
    )
    (net (code "73") (name "Net-(R11-Pad1)") (class "Default")
      (node (ref "R11") (pin "1") (pinfunction "1_1") (pintype "passive"))
      (node (ref "X15") (pin "2") (pinfunction "2_2") (pintype "bidirectional"))
    )
    (net (code "74") (name "Net-(U1A-+IN)") (class "Default")
      (node (ref "R10") (pin "2") (pinfunction "2_2") (pintype "passive"))
      (node (ref "U1") (pin "3") (pinfunction "+IN_3") (pintype "input"))
    )
    (net (code "75") (name "Net-(U1B-+IN)") (class "Default")
      (node (ref "R11") (pin "2") (pinfunction "2_2") (pintype "passive"))
      (node (ref "U1") (pin "5") (pinfunction "+IN_5") (pintype "input"))
    )
    (net (code "76") (name "RXD") (class "Default")
      (node (ref "R13") (pin "2") (pinfunction "2_2") (pintype "passive"))
      (node (ref "X17") (pin "3") (pinfunction "3_3") (pintype "bidirectional"))
    )
    (net (code "77") (name "SCL") (class "Default")
      (node (ref "IC1") (pin "12") (pinfunction "SCL_12") (pintype "input"))
      (node (ref "MS1") (pin "18") (pinfunction "GPIOSCL_18") (pintype "bidirectional"))
      (node (ref "R8") (pin "1") (pinfunction "1_1") (pintype "passive"))
    )
    (net (code "78") (name "SDA") (class "Default")
      (node (ref "IC1") (pin "13") (pinfunction "SDA_13") (pintype "bidirectional"))
      (node (ref "MS1") (pin "17") (pinfunction "GPIOSDA_17") (pintype "bidirectional"))
      (node (ref "R5") (pin "1") (pinfunction "1_1") (pintype "passive"))
    )
    (net (code "79") (name "SERVO_1") (class "Default")
      (node (ref "MS1") (pin "23") (pinfunction "GPIO11_23") (pintype "bidirectional"))
      (node (ref "R6") (pin "2") (pinfunction "2_2") (pintype "passive"))
    )
    (net (code "80") (name "SERVO_2") (class "Default")
      (node (ref "MS1") (pin "24") (pinfunction "GPIO12_24") (pintype "bidirectional"))
      (node (ref "R7") (pin "2") (pinfunction "2_2") (pintype "passive"))
    )
    (net (code "81") (name "TXD") (class "Default")
      (node (ref "R12") (pin "2") (pinfunction "2_2") (pintype "passive"))
      (node (ref "X17") (pin "2") (pinfunction "2_2") (pintype "bidirectional"))
    )
    (net (code "82") (name "VBUS") (class "Default")
      (node (ref "JP1") (pin "1") (pinfunction "1_1") (pintype "passive"))
      (node (ref "MS1") (pin "26") (pinfunction "USB_26") (pintype "power_in"))
    )
    (net (code "83") (name "unconnected-(IC1-INTA-Pad20)") (class "Default")
      (node (ref "IC1") (pin "20") (pinfunction "INTA_20") (pintype "output"))
    )
    (net (code "84") (name "unconnected-(IC1-INTB-Pad19)") (class "Default")
      (node (ref "IC1") (pin "19") (pinfunction "INTB_19") (pintype "output"))
    )
    (net (code "85") (name "unconnected-(MS1-AREF-Pad3)") (class "Default")
      (node (ref "MS1") (pin "3") (pinfunction "AREF_3") (pintype "passive"))
    )
    (net (code "86") (name "unconnected-(MS1-EN-Pad27)") (class "Default")
      (node (ref "MS1") (pin "27") (pinfunction "EN_27") (pintype "passive"))
    )
    (net (code "87") (name "unconnected-(MS1-NC-Pad16)") (class "Default")
      (node (ref "MS1") (pin "16") (pinfunction "NC_16") (pintype "passive"))
    )
    (net (code "88") (name "unconnected-(MS1-~{RESET}-Pad1)") (class "Default")
      (node (ref "MS1") (pin "1") (pinfunction "~{RESET}_1") (pintype "input"))
    )
  )
)
